# STSPIN32F0A_ESC1.net
KiCad netlist of a schematic drawn in Altium Designer
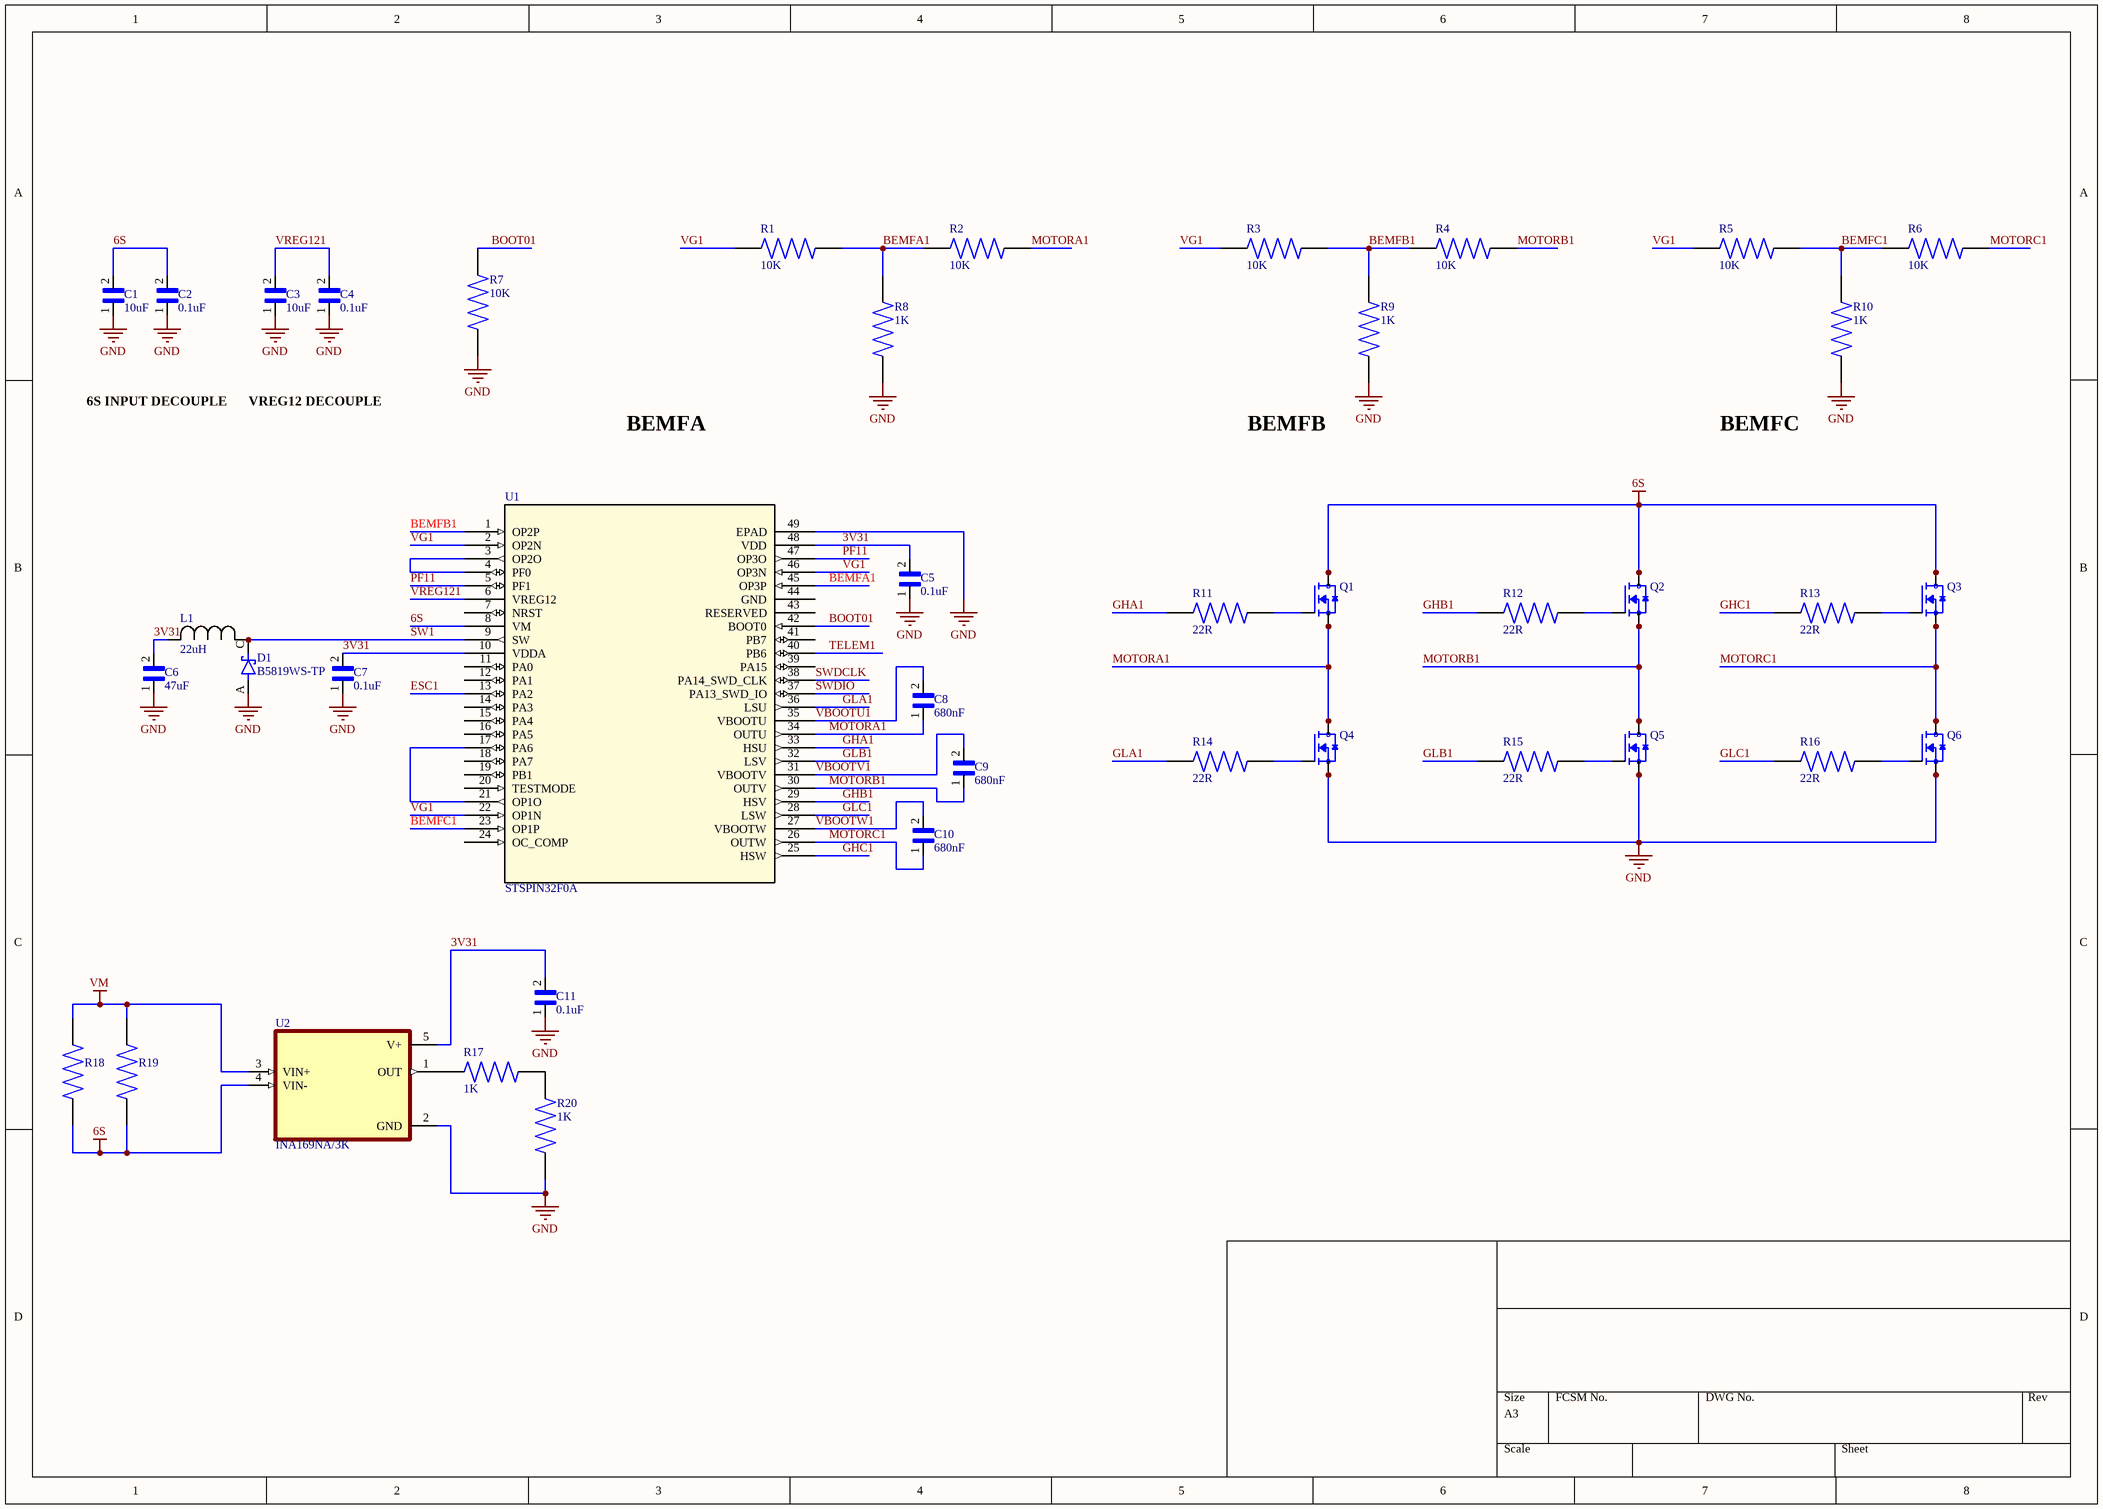
[diagram p0: STSPIN32F0A ESC1.SchDoc]

(export (version "E")
  (design (tool "Eeschema 10.0.6"))
  (components
    (comp (ref "C1")
      (value "10uF")
      (footprint "CAPC1608X100N")
      (description "Capacitor 0603 0.1uF Y5V")
      (fields (field (name "MP") "CL10F104ZB8NNNC") (field (name "MF") "{'manufacturer': u'Samsung'}"))
      (libsource (lib "SnapEDA_Library") (part "CL10F104ZB8NNNC"))
    )
    (comp (ref "C2")
      (value "0.1uF")
      (footprint "CAPC1005X55N")
      (fields (field (name "MP") "GRM1555C1H222JA01D"))
      (libsource (lib "GRM1555C1H222JA01D") (part "GRM1555C1H222JA01D"))
    )
    (comp (ref "C3")
      (value "10uF")
      (footprint "CAPC1608X100N")
      (description "Capacitor 0603 0.1uF Y5V")
      (fields (field (name "MP") "CL10F104ZB8NNNC") (field (name "MF") "{'manufacturer': u'Samsung'}"))
      (libsource (lib "SnapEDA_Library") (part "CL10F104ZB8NNNC"))
    )
    (comp (ref "C4")
      (value "0.1uF")
      (footprint "CAPC1005X55N")
      (fields (field (name "MP") "GRM1555C1H222JA01D"))
      (libsource (lib "GRM1555C1H222JA01D") (part "GRM1555C1H222JA01D"))
    )
    (comp (ref "C5")
      (value "0.1uF")
      (footprint "CAPC1005X55N")
      (fields (field (name "MP") "GRM1555C1H222JA01D"))
      (libsource (lib "GRM1555C1H222JA01D") (part "GRM1555C1H222JA01D"))
    )
    (comp (ref "C6")
      (value "47uF")
      (footprint "CAPC1608X90N")
      (description "SMD Capacitor X7R(EIA) with Capacitance: 0.22uF Tol. 5%. Rated Voltage: 25Vdc")
      (fields (field (name "MP") "GRM188R71E224JA88D"))
      (libsource (lib "GRM188R71E224JA88D") (part "GRM188R71E224JA88D"))
    )
    (comp (ref "C7")
      (value "0.1uF")
      (footprint "CAPC1005X55N")
      (fields (field (name "MP") "GRM1555C1H222JA01D"))
      (libsource (lib "GRM1555C1H222JA01D") (part "GRM1555C1H222JA01D"))
    )
    (comp (ref "C8")
      (value "680nF")
      (footprint "CAPC1005X55N")
      (fields (field (name "MP") "GRM1555C1H222JA01D"))
      (libsource (lib "GRM1555C1H222JA01D") (part "GRM1555C1H222JA01D"))
    )
    (comp (ref "C9")
      (value "680nF")
      (footprint "CAPC1005X55N")
      (fields (field (name "MP") "GRM1555C1H222JA01D"))
      (libsource (lib "GRM1555C1H222JA01D") (part "GRM1555C1H222JA01D"))
    )
    (comp (ref "C10")
      (value "680nF")
      (footprint "CAPC1005X55N")
      (fields (field (name "MP") "GRM1555C1H222JA01D"))
      (libsource (lib "GRM1555C1H222JA01D") (part "GRM1555C1H222JA01D"))
    )
    (comp (ref "C11")
      (value "0.1uF")
      (footprint "CAPC1005X55N")
      (fields (field (name "MP") "GRM1555C1H222JA01D"))
      (libsource (lib "GRM1555C1H222JA01D") (part "GRM1555C1H222JA01D"))
    )
    (comp (ref "D1")
      (value "B5819WS-TP")
      (footprint "SOD2512X115N")
      (fields (field (name "MF") "{'manufacturer': u'Micro Commercial Components'}"))
      (libsource (lib "SnapEDA_Library") (part "B5819WS-TP"))
    )
    (comp (ref "L1")
      (value "22uH")
      (footprint "IND_BOURNS_SRN3015")
      (description "No Description Available")
      (fields
        (field (name "MANUFACTURER_PART_NUMBER") "SRN3015-220M")
        (field (name "COPYRIGHT") "Copyright (C) 2022 Ultra Librarian. All rights reserved.")
      )
      (libsource (lib "SRN3015-220M") (part "SRN3015-220M"))
    )
    (comp (ref "Q1")
      (value "TPHR8504PL,L1Q")
      (footprint "TRANS_TPHR8504PL,L1Q")
      (description "N-Channel 40V 150A (Tc) 1W (Ta), 170W (Tc) Surface Mount 8-SOP Advance (5x5)")
      (fields (field (name "MF") "Toshiba Semiconductor"))
      (libsource (lib "TPHR8504PL_L1Q") (part "TPHR8504PL,L1Q"))
    )
    (comp (ref "Q2")
      (value "TPHR8504PL,L1Q")
      (footprint "TRANS_TPHR8504PL,L1Q")
      (description "N-Channel 40V 150A (Tc) 1W (Ta), 170W (Tc) Surface Mount 8-SOP Advance (5x5)")
      (fields (field (name "MF") "Toshiba Semiconductor"))
      (libsource (lib "TPHR8504PL_L1Q") (part "TPHR8504PL,L1Q"))
    )
    (comp (ref "Q3")
      (value "TPHR8504PL,L1Q")
      (footprint "TRANS_TPHR8504PL,L1Q")
      (description "N-Channel 40V 150A (Tc) 1W (Ta), 170W (Tc) Surface Mount 8-SOP Advance (5x5)")
      (fields (field (name "MF") "Toshiba Semiconductor"))
      (libsource (lib "TPHR8504PL_L1Q") (part "TPHR8504PL,L1Q"))
    )
    (comp (ref "Q4")
      (value "TPHR8504PL,L1Q")
      (footprint "TRANS_TPHR8504PL,L1Q")
      (description "N-Channel 40V 150A (Tc) 1W (Ta), 170W (Tc) Surface Mount 8-SOP Advance (5x5)")
      (fields (field (name "MF") "Toshiba Semiconductor"))
      (libsource (lib "TPHR8504PL_L1Q") (part "TPHR8504PL,L1Q"))
    )
    (comp (ref "Q5")
      (value "TPHR8504PL,L1Q")
      (footprint "TRANS_TPHR8504PL,L1Q")
      (description "N-Channel 40V 150A (Tc) 1W (Ta), 170W (Tc) Surface Mount 8-SOP Advance (5x5)")
      (fields (field (name "MF") "Toshiba Semiconductor"))
      (libsource (lib "TPHR8504PL_L1Q") (part "TPHR8504PL,L1Q"))
    )
    (comp (ref "Q6")
      (value "TPHR8504PL,L1Q")
      (footprint "TRANS_TPHR8504PL,L1Q")
      (description "N-Channel 40V 150A (Tc) 1W (Ta), 170W (Tc) Surface Mount 8-SOP Advance (5x5)")
      (fields (field (name "MF") "Toshiba Semiconductor"))
      (libsource (lib "TPHR8504PL_L1Q") (part "TPHR8504PL,L1Q"))
    )
    (comp (ref "R1")
      (value "10K")
      (footprint "RESC1005X37N")
      (fields (field (name "MP") "RE0402BRE07330KL") (field (name "MF") "{'manufacturer': u'Yageo'}"))
      (libsource (lib "SnapEDA_Library") (part "RE0402BRE07330KL"))
    )
    (comp (ref "R2")
      (value "10K")
      (footprint "RESC1005X37N")
      (fields (field (name "MP") "RE0402BRE07330KL") (field (name "MF") "{'manufacturer': u'Yageo'}"))
      (libsource (lib "SnapEDA_Library") (part "RE0402BRE07330KL"))
    )
    (comp (ref "R3")
      (value "10K")
      (footprint "RESC1005X37N")
      (fields (field (name "MP") "RE0402BRE07330KL") (field (name "MF") "{'manufacturer': u'Yageo'}"))
      (libsource (lib "SnapEDA_Library") (part "RE0402BRE07330KL"))
    )
    (comp (ref "R4")
      (value "10K")
      (footprint "RESC1005X37N")
      (fields (field (name "MP") "RE0402BRE07330KL") (field (name "MF") "{'manufacturer': u'Yageo'}"))
      (libsource (lib "SnapEDA_Library") (part "RE0402BRE07330KL"))
    )
    (comp (ref "R5")
      (value "10K")
      (footprint "RESC1005X37N")
      (fields (field (name "MP") "RE0402BRE07330KL") (field (name "MF") "{'manufacturer': u'Yageo'}"))
      (libsource (lib "SnapEDA_Library") (part "RE0402BRE07330KL"))
    )
    (comp (ref "R6")
      (value "10K")
      (footprint "RESC1005X37N")
      (fields (field (name "MP") "RE0402BRE07330KL") (field (name "MF") "{'manufacturer': u'Yageo'}"))
      (libsource (lib "SnapEDA_Library") (part "RE0402BRE07330KL"))
    )
    (comp (ref "R7")
      (value "10K")
      (footprint "RESC1005X37N")
      (fields (field (name "MP") "RE0402BRE07330KL") (field (name "MF") "{'manufacturer': u'Yageo'}"))
      (libsource (lib "SnapEDA_Library") (part "RE0402BRE07330KL"))
    )
    (comp (ref "R8")
      (value "1K")
      (footprint "RESC1005X37N")
      (fields (field (name "MP") "RE0402BRE07330KL") (field (name "MF") "{'manufacturer': u'Yageo'}"))
      (libsource (lib "SnapEDA_Library") (part "RE0402BRE07330KL"))
    )
    (comp (ref "R9")
      (value "1K")
      (footprint "RESC1005X37N")
      (fields (field (name "MP") "RE0402BRE07330KL") (field (name "MF") "{'manufacturer': u'Yageo'}"))
      (libsource (lib "SnapEDA_Library") (part "RE0402BRE07330KL"))
    )
    (comp (ref "R10")
      (value "1K")
      (footprint "RESC1005X37N")
      (fields (field (name "MP") "RE0402BRE07330KL") (field (name "MF") "{'manufacturer': u'Yageo'}"))
      (libsource (lib "SnapEDA_Library") (part "RE0402BRE07330KL"))
    )
    (comp (ref "R11")
      (value "22R")
      (footprint "RESC1005X37N")
      (fields (field (name "MP") "RE0402BRE07330KL") (field (name "MF") "{'manufacturer': u'Yageo'}"))
      (libsource (lib "SnapEDA_Library") (part "RE0402BRE07330KL"))
    )
    (comp (ref "R12")
      (value "22R")
      (footprint "RESC1005X37N")
      (fields (field (name "MP") "RE0402BRE07330KL") (field (name "MF") "{'manufacturer': u'Yageo'}"))
      (libsource (lib "SnapEDA_Library") (part "RE0402BRE07330KL"))
    )
    (comp (ref "R13")
      (value "22R")
      (footprint "RESC1005X37N")
      (fields (field (name "MP") "RE0402BRE07330KL") (field (name "MF") "{'manufacturer': u'Yageo'}"))
      (libsource (lib "SnapEDA_Library") (part "RE0402BRE07330KL"))
    )
    (comp (ref "R14")
      (value "22R")
      (footprint "RESC1005X37N")
      (fields (field (name "MP") "RE0402BRE07330KL") (field (name "MF") "{'manufacturer': u'Yageo'}"))
      (libsource (lib "SnapEDA_Library") (part "RE0402BRE07330KL"))
    )
    (comp (ref "R15")
      (value "22R")
      (footprint "RESC1005X37N")
      (fields (field (name "MP") "RE0402BRE07330KL") (field (name "MF") "{'manufacturer': u'Yageo'}"))
      (libsource (lib "SnapEDA_Library") (part "RE0402BRE07330KL"))
    )
    (comp (ref "R16")
      (value "22R")
      (footprint "RESC1005X37N")
      (fields (field (name "MP") "RE0402BRE07330KL") (field (name "MF") "{'manufacturer': u'Yageo'}"))
      (libsource (lib "SnapEDA_Library") (part "RE0402BRE07330KL"))
    )
    (comp (ref "R17")
      (value "1K")
      (footprint "RESC1005X37N")
      (fields (field (name "MP") "RE0402BRE07330KL") (field (name "MF") "{'manufacturer': u'Yageo'}"))
      (libsource (lib "SnapEDA_Library") (part "RE0402BRE07330KL"))
    )
    (comp (ref "R18")
      (value "CSSH2512JTL500")
      (footprint "RESC6232X104N")
      (fields (field (name "MF") "{'manufacturer': u'Stackpole Electronics Inc'}"))
      (libsource (lib "SnapEDA_Library") (part "CSSH2512JTL500"))
    )
    (comp (ref "R19")
      (value "CSSH2512JTL500")
      (footprint "RESC6232X104N")
      (fields (field (name "MF") "{'manufacturer': u'Stackpole Electronics Inc'}"))
      (libsource (lib "SnapEDA_Library") (part "CSSH2512JTL500"))
    )
    (comp (ref "R20")
      (value "1K")
      (footprint "RESC1005X37N")
      (fields (field (name "MP") "RE0402BRE07330KL") (field (name "MF") "{'manufacturer': u'Yageo'}"))
      (libsource (lib "SnapEDA_Library") (part "RE0402BRE07330KL"))
    )
    (comp (ref "U1")
      (value "STSPIN32F0A")
      (footprint "VFQFPN-48_7x7x1mm_STM-L")
      (description "No Description Available")
      (fields (field (name "COPYRIGHT") "Copyright (C) 2022 Ultra Librarian. All rights reserved."))
      (libsource (lib "STSPIN32F0A") (part "STSPIN32F0A"))
    )
    (comp (ref "U2")
      (value "INA169NA/3K")
      (footprint "SOT95P280X145-5N")
      (fields (field (name "MF") "{'manufacturer': u'Texas Instruments'}"))
      (libsource (lib "SnapEDA_Library") (part "INA169NA/3K"))
    )
  )
  (nets
    (net (code "1") (name "/3V31") (class "Default")
      (node (ref "C11") (pin "2") (pinfunction "2_2") (pintype "passive"))
      (node (ref "C5") (pin "2") (pinfunction "2_2") (pintype "passive"))
      (node (ref "C6") (pin "2") (pinfunction "2_2") (pintype "passive"))
      (node (ref "C7") (pin "2") (pinfunction "2_2") (pintype "passive"))
      (node (ref "L1") (pin "2") (pinfunction "2_2") (pintype "passive"))
      (node (ref "U1") (pin "10") (pinfunction "VDDA_10") (pintype "power_in"))
      (node (ref "U1") (pin "48") (pinfunction "VDD_48") (pintype "power_in"))
      (node (ref "U2") (pin "5") (pinfunction "V+_5") (pintype "power_in"))
    )
    (net (code "2") (name "/BEMFA1") (class "Default")
      (node (ref "R1") (pin "1") (pinfunction "1_1") (pintype "passive"))
      (node (ref "R2") (pin "2") (pinfunction "2_2") (pintype "passive"))
      (node (ref "R8") (pin "1") (pinfunction "1_1") (pintype "passive"))
      (node (ref "U1") (pin "45") (pinfunction "OP3P_45") (pintype "input"))
    )
    (net (code "3") (name "/BEMFB1") (class "Default")
      (node (ref "R3") (pin "1") (pinfunction "1_1") (pintype "passive"))
      (node (ref "R4") (pin "2") (pinfunction "2_2") (pintype "passive"))
      (node (ref "R9") (pin "1") (pinfunction "1_1") (pintype "passive"))
      (node (ref "U1") (pin "1") (pinfunction "OP2P_1") (pintype "input"))
    )
    (net (code "4") (name "/BEMFC1") (class "Default")
      (node (ref "R10") (pin "1") (pinfunction "1_1") (pintype "passive"))
      (node (ref "R5") (pin "1") (pinfunction "1_1") (pintype "passive"))
      (node (ref "R6") (pin "2") (pinfunction "2_2") (pintype "passive"))
      (node (ref "U1") (pin "23") (pinfunction "OP1P_23") (pintype "input"))
    )
    (net (code "5") (name "/BOOT01") (class "Default")
      (node (ref "R7") (pin "2") (pinfunction "2_2") (pintype "passive"))
      (node (ref "U1") (pin "42") (pinfunction "BOOT0_42") (pintype "input"))
    )
    (net (code "6") (name "/ESC1") (class "Default")
      (node (ref "U1") (pin "13") (pinfunction "PA2_13") (pintype "bidirectional"))
    )
    (net (code "7") (name "/GHA1") (class "Default")
      (node (ref "R11") (pin "2") (pinfunction "2_2") (pintype "passive"))
      (node (ref "U1") (pin "33") (pinfunction "HSU_33") (pintype "output"))
    )
    (net (code "8") (name "/GHB1") (class "Default")
      (node (ref "R12") (pin "2") (pinfunction "2_2") (pintype "passive"))
      (node (ref "U1") (pin "29") (pinfunction "HSV_29") (pintype "output"))
    )
    (net (code "9") (name "/GHC1") (class "Default")
      (node (ref "R13") (pin "2") (pinfunction "2_2") (pintype "passive"))
      (node (ref "U1") (pin "25") (pinfunction "HSW_25") (pintype "output"))
    )
    (net (code "10") (name "/GLA1") (class "Default")
      (node (ref "R14") (pin "2") (pinfunction "2_2") (pintype "passive"))
      (node (ref "U1") (pin "36") (pinfunction "LSU_36") (pintype "output"))
    )
    (net (code "11") (name "/GLB1") (class "Default")
      (node (ref "R15") (pin "2") (pinfunction "2_2") (pintype "passive"))
      (node (ref "U1") (pin "32") (pinfunction "LSV_32") (pintype "output"))
    )
    (net (code "12") (name "/GLC1") (class "Default")
      (node (ref "R16") (pin "2") (pinfunction "2_2") (pintype "passive"))
      (node (ref "U1") (pin "28") (pinfunction "LSW_28") (pintype "output"))
    )
    (net (code "13") (name "/MOTORA1") (class "Default")
      (node (ref "C8") (pin "1") (pinfunction "1_1") (pintype "passive"))
      (node (ref "Q1") (pin "1") (pinfunction "S_1") (pintype "passive"))
      (node (ref "Q1") (pin "2") (pinfunction "S_2") (pintype "passive"))
      (node (ref "Q1") (pin "3") (pinfunction "S_3") (pintype "passive"))
      (node (ref "Q4") (pin "5") (pinfunction "D_5") (pintype "passive"))
      (node (ref "Q4") (pin "6") (pinfunction "D_6") (pintype "passive"))
      (node (ref "Q4") (pin "7") (pinfunction "D_7") (pintype "passive"))
      (node (ref "Q4") (pin "8") (pinfunction "D_8") (pintype "passive"))
      (node (ref "Q4") (pin "9") (pinfunction "D_9") (pintype "passive"))
      (node (ref "R2") (pin "1") (pinfunction "1_1") (pintype "passive"))
      (node (ref "U1") (pin "34") (pinfunction "OUTU_34") (pintype "output"))
    )
    (net (code "14") (name "/MOTORB1") (class "Default")
      (node (ref "C9") (pin "1") (pinfunction "1_1") (pintype "passive"))
      (node (ref "Q2") (pin "1") (pinfunction "S_1") (pintype "passive"))
      (node (ref "Q2") (pin "2") (pinfunction "S_2") (pintype "passive"))
      (node (ref "Q2") (pin "3") (pinfunction "S_3") (pintype "passive"))
      (node (ref "Q5") (pin "5") (pinfunction "D_5") (pintype "passive"))
      (node (ref "Q5") (pin "6") (pinfunction "D_6") (pintype "passive"))
      (node (ref "Q5") (pin "7") (pinfunction "D_7") (pintype "passive"))
      (node (ref "Q5") (pin "8") (pinfunction "D_8") (pintype "passive"))
      (node (ref "Q5") (pin "9") (pinfunction "D_9") (pintype "passive"))
      (node (ref "R4") (pin "1") (pinfunction "1_1") (pintype "passive"))
      (node (ref "U1") (pin "30") (pinfunction "OUTV_30") (pintype "output"))
    )
    (net (code "15") (name "/MOTORC1") (class "Default")
      (node (ref "C10") (pin "1") (pinfunction "1_1") (pintype "passive"))
      (node (ref "Q3") (pin "1") (pinfunction "S_1") (pintype "passive"))
      (node (ref "Q3") (pin "2") (pinfunction "S_2") (pintype "passive"))
      (node (ref "Q3") (pin "3") (pinfunction "S_3") (pintype "passive"))
      (node (ref "Q6") (pin "5") (pinfunction "D_5") (pintype "passive"))
      (node (ref "Q6") (pin "6") (pinfunction "D_6") (pintype "passive"))
      (node (ref "Q6") (pin "7") (pinfunction "D_7") (pintype "passive"))
      (node (ref "Q6") (pin "8") (pinfunction "D_8") (pintype "passive"))
      (node (ref "Q6") (pin "9") (pinfunction "D_9") (pintype "passive"))
      (node (ref "R6") (pin "1") (pinfunction "1_1") (pintype "passive"))
      (node (ref "U1") (pin "26") (pinfunction "OUTW_26") (pintype "output"))
    )
    (net (code "16") (name "/PF11") (class "Default")
      (node (ref "U1") (pin "47") (pinfunction "OP3O_47") (pintype "output"))
      (node (ref "U1") (pin "5") (pinfunction "PF1_5") (pintype "bidirectional"))
    )
    (net (code "17") (name "/SW1") (class "Default")
      (node (ref "D1") (pin "C") (pinfunction "K_C") (pintype "passive"))
      (node (ref "L1") (pin "1") (pinfunction "1_1") (pintype "passive"))
      (node (ref "U1") (pin "9") (pinfunction "SW_9") (pintype "output"))
    )
    (net (code "18") (name "/SWDCLK") (class "Default")
      (node (ref "U1") (pin "38") (pinfunction "PA14_SWD_CLK_38") (pintype "bidirectional"))
    )
    (net (code "19") (name "/SWDIO") (class "Default")
      (node (ref "U1") (pin "37") (pinfunction "PA13_SWD_IO_37") (pintype "bidirectional"))
    )
    (net (code "20") (name "/TELEM1") (class "Default")
      (node (ref "U1") (pin "40") (pinfunction "PB6_40") (pintype "bidirectional"))
    )
    (net (code "21") (name "/VBOOTU1") (class "Default")
      (node (ref "C8") (pin "2") (pinfunction "2_2") (pintype "passive"))
      (node (ref "U1") (pin "35") (pinfunction "VBOOTU_35") (pintype "power_in"))
    )
    (net (code "22") (name "/VBOOTV1") (class "Default")
      (node (ref "C9") (pin "2") (pinfunction "2_2") (pintype "passive"))
      (node (ref "U1") (pin "31") (pinfunction "VBOOTV_31") (pintype "power_in"))
    )
    (net (code "23") (name "/VBOOTW1") (class "Default")
      (node (ref "C10") (pin "2") (pinfunction "2_2") (pintype "passive"))
      (node (ref "U1") (pin "27") (pinfunction "VBOOTW_27") (pintype "power_in"))
    )
    (net (code "24") (name "/VG1") (class "Default")
      (node (ref "R1") (pin "2") (pinfunction "2_2") (pintype "passive"))
      (node (ref "R3") (pin "2") (pinfunction "2_2") (pintype "passive"))
      (node (ref "R5") (pin "2") (pinfunction "2_2") (pintype "passive"))
      (node (ref "U1") (pin "2") (pinfunction "OP2N_2") (pintype "input"))
      (node (ref "U1") (pin "22") (pinfunction "OP1N_22") (pintype "input"))
      (node (ref "U1") (pin "46") (pinfunction "OP3N_46") (pintype "input"))
    )
    (net (code "25") (name "/VREG121") (class "Default")
      (node (ref "C3") (pin "2") (pinfunction "2_2") (pintype "passive"))
      (node (ref "C4") (pin "2") (pinfunction "2_2") (pintype "passive"))
      (node (ref "U1") (pin "6") (pinfunction "VREG12_6") (pintype "power_in"))
    )
    (net (code "26") (name "6S") (class "Default")
      (node (ref "C1") (pin "2") (pinfunction "2_2") (pintype "passive"))
      (node (ref "C2") (pin "2") (pinfunction "2_2") (pintype "passive"))
      (node (ref "Q1") (pin "5") (pinfunction "D_5") (pintype "passive"))
      (node (ref "Q1") (pin "6") (pinfunction "D_6") (pintype "passive"))
      (node (ref "Q1") (pin "7") (pinfunction "D_7") (pintype "passive"))
      (node (ref "Q1") (pin "8") (pinfunction "D_8") (pintype "passive"))
      (node (ref "Q1") (pin "9") (pinfunction "D_9") (pintype "passive"))
      (node (ref "Q2") (pin "5") (pinfunction "D_5") (pintype "passive"))
      (node (ref "Q2") (pin "6") (pinfunction "D_6") (pintype "passive"))
      (node (ref "Q2") (pin "7") (pinfunction "D_7") (pintype "passive"))
      (node (ref "Q2") (pin "8") (pinfunction "D_8") (pintype "passive"))
      (node (ref "Q2") (pin "9") (pinfunction "D_9") (pintype "passive"))
      (node (ref "Q3") (pin "5") (pinfunction "D_5") (pintype "passive"))
      (node (ref "Q3") (pin "6") (pinfunction "D_6") (pintype "passive"))
      (node (ref "Q3") (pin "7") (pinfunction "D_7") (pintype "passive"))
      (node (ref "Q3") (pin "8") (pinfunction "D_8") (pintype "passive"))
      (node (ref "Q3") (pin "9") (pinfunction "D_9") (pintype "passive"))
      (node (ref "R18") (pin "2") (pinfunction "2_2") (pintype "passive"))
      (node (ref "R19") (pin "2") (pinfunction "2_2") (pintype "passive"))
      (node (ref "U1") (pin "8") (pinfunction "VM_8") (pintype "power_in"))
      (node (ref "U2") (pin "4") (pinfunction "VIN-_4") (pintype "input"))
    )
    (net (code "27") (name "GND") (class "Default")
      (node (ref "C1") (pin "1") (pinfunction "1_1") (pintype "passive"))
      (node (ref "C11") (pin "1") (pinfunction "1_1") (pintype "passive"))
      (node (ref "C2") (pin "1") (pinfunction "1_1") (pintype "passive"))
      (node (ref "C3") (pin "1") (pinfunction "1_1") (pintype "passive"))
      (node (ref "C4") (pin "1") (pinfunction "1_1") (pintype "passive"))
      (node (ref "C5") (pin "1") (pinfunction "1_1") (pintype "passive"))
      (node (ref "C6") (pin "1") (pinfunction "1_1") (pintype "passive"))
      (node (ref "C7") (pin "1") (pinfunction "1_1") (pintype "passive"))
      (node (ref "D1") (pin "A") (pinfunction "A_A") (pintype "passive"))
      (node (ref "Q4") (pin "1") (pinfunction "S_1") (pintype "passive"))
      (node (ref "Q4") (pin "2") (pinfunction "S_2") (pintype "passive"))
      (node (ref "Q4") (pin "3") (pinfunction "S_3") (pintype "passive"))
      (node (ref "Q5") (pin "1") (pinfunction "S_1") (pintype "passive"))
      (node (ref "Q5") (pin "2") (pinfunction "S_2") (pintype "passive"))
      (node (ref "Q5") (pin "3") (pinfunction "S_3") (pintype "passive"))
      (node (ref "Q6") (pin "1") (pinfunction "S_1") (pintype "passive"))
      (node (ref "Q6") (pin "2") (pinfunction "S_2") (pintype "passive"))
      (node (ref "Q6") (pin "3") (pinfunction "S_3") (pintype "passive"))
      (node (ref "R10") (pin "2") (pinfunction "2_2") (pintype "passive"))
      (node (ref "R20") (pin "2") (pinfunction "2_2") (pintype "passive"))
      (node (ref "R7") (pin "1") (pinfunction "1_1") (pintype "passive"))
      (node (ref "R8") (pin "2") (pinfunction "2_2") (pintype "passive"))
      (node (ref "R9") (pin "2") (pinfunction "2_2") (pintype "passive"))
      (node (ref "U1") (pin "49") (pinfunction "EPAD_49") (pintype "passive"))
      (node (ref "U2") (pin "2") (pinfunction "GND_2") (pintype "power_in"))
    )
    (net (code "28") (name "Net-(Q1-G)") (class "Default")
      (node (ref "Q1") (pin "4") (pinfunction "G_4") (pintype "passive"))
      (node (ref "R11") (pin "1") (pinfunction "1_1") (pintype "passive"))
    )
    (net (code "29") (name "Net-(Q2-G)") (class "Default")
      (node (ref "Q2") (pin "4") (pinfunction "G_4") (pintype "passive"))
      (node (ref "R12") (pin "1") (pinfunction "1_1") (pintype "passive"))
    )
    (net (code "30") (name "Net-(Q3-G)") (class "Default")
      (node (ref "Q3") (pin "4") (pinfunction "G_4") (pintype "passive"))
      (node (ref "R13") (pin "1") (pinfunction "1_1") (pintype "passive"))
    )
    (net (code "31") (name "Net-(Q4-G)") (class "Default")
      (node (ref "Q4") (pin "4") (pinfunction "G_4") (pintype "passive"))
      (node (ref "R14") (pin "1") (pinfunction "1_1") (pintype "passive"))
    )
    (net (code "32") (name "Net-(Q5-G)") (class "Default")
      (node (ref "Q5") (pin "4") (pinfunction "G_4") (pintype "passive"))
      (node (ref "R15") (pin "1") (pinfunction "1_1") (pintype "passive"))
    )
    (net (code "33") (name "Net-(Q6-G)") (class "Default")
      (node (ref "Q6") (pin "4") (pinfunction "G_4") (pintype "passive"))
      (node (ref "R16") (pin "1") (pinfunction "1_1") (pintype "passive"))
    )
    (net (code "34") (name "Net-(R17-Pad2)") (class "Default")
      (node (ref "R17") (pin "2") (pinfunction "2_2") (pintype "passive"))
      (node (ref "R20") (pin "1") (pinfunction "1_1") (pintype "passive"))
    )
    (net (code "35") (name "Net-(U1-OP1O)") (class "Default")
      (node (ref "U1") (pin "17") (pinfunction "PA6_17") (pintype "bidirectional"))
      (node (ref "U1") (pin "21") (pinfunction "OP1O_21") (pintype "output"))
    )
    (net (code "36") (name "Net-(U1-OP2O)") (class "Default")
      (node (ref "U1") (pin "3") (pinfunction "OP2O_3") (pintype "output"))
      (node (ref "U1") (pin "4") (pinfunction "PF0_4") (pintype "bidirectional"))
    )
    (net (code "37") (name "Net-(U2-OUT)") (class "Default")
      (node (ref "R17") (pin "1") (pinfunction "1_1") (pintype "passive"))
      (node (ref "U2") (pin "1") (pinfunction "OUT_1") (pintype "output"))
    )
    (net (code "38") (name "VM") (class "Default")
      (node (ref "R18") (pin "1") (pinfunction "1_1") (pintype "passive"))
      (node (ref "R19") (pin "1") (pinfunction "1_1") (pintype "passive"))
      (node (ref "U2") (pin "3") (pinfunction "VIN+_3") (pintype "input"))
    )
    (net (code "39") (name "unconnected-(U1-GND-Pad44)") (class "Default")
      (node (ref "U1") (pin "44") (pinfunction "GND_44") (pintype "power_in"))
    )
    (net (code "40") (name "unconnected-(U1-NRST-Pad7)") (class "Default")
      (node (ref "U1") (pin "7") (pinfunction "NRST_7") (pintype "bidirectional"))
    )
    (net (code "41") (name "unconnected-(U1-OC_COMP-Pad24)") (class "Default")
      (node (ref "U1") (pin "24") (pinfunction "OC_COMP_24") (pintype "input"))
    )
    (net (code "42") (name "unconnected-(U1-PA0-Pad11)") (class "Default")
      (node (ref "U1") (pin "11") (pinfunction "PA0_11") (pintype "bidirectional"))
    )
    (net (code "43") (name "unconnected-(U1-PA1-Pad12)") (class "Default")
      (node (ref "U1") (pin "12") (pinfunction "PA1_12") (pintype "bidirectional"))
    )
    (net (code "44") (name "unconnected-(U1-PA3-Pad14)") (class "Default")
      (node (ref "U1") (pin "14") (pinfunction "PA3_14") (pintype "bidirectional"))
    )
    (net (code "45") (name "unconnected-(U1-PA4-Pad15)") (class "Default")
      (node (ref "U1") (pin "15") (pinfunction "PA4_15") (pintype "bidirectional"))
    )
    (net (code "46") (name "unconnected-(U1-PA5-Pad16)") (class "Default")
      (node (ref "U1") (pin "16") (pinfunction "PA5_16") (pintype "bidirectional"))
    )
    (net (code "47") (name "unconnected-(U1-PA7-Pad18)") (class "Default")
      (node (ref "U1") (pin "18") (pinfunction "PA7_18") (pintype "bidirectional"))
    )
    (net (code "48") (name "unconnected-(U1-PA15-Pad39)") (class "Default")
      (node (ref "U1") (pin "39") (pinfunction "PA15_39") (pintype "bidirectional"))
    )
    (net (code "49") (name "unconnected-(U1-PB1-Pad19)") (class "Default")
      (node (ref "U1") (pin "19") (pinfunction "PB1_19") (pintype "bidirectional"))
    )
    (net (code "50") (name "unconnected-(U1-PB7-Pad41)") (class "Default")
      (node (ref "U1") (pin "41") (pinfunction "PB7_41") (pintype "bidirectional"))
    )
    (net (code "51") (name "unconnected-(U1-RESERVED-Pad43)") (class "Default")
      (node (ref "U1") (pin "43") (pinfunction "RESERVED_43") (pintype "passive"))
    )
    (net (code "52") (name "unconnected-(U1-TESTMODE-Pad20)") (class "Default")
      (node (ref "U1") (pin "20") (pinfunction "TESTMODE_20") (pintype "input"))
    )
  )
)
